# References.net
KiCad netlist of a schematic drawn in Altium Designer
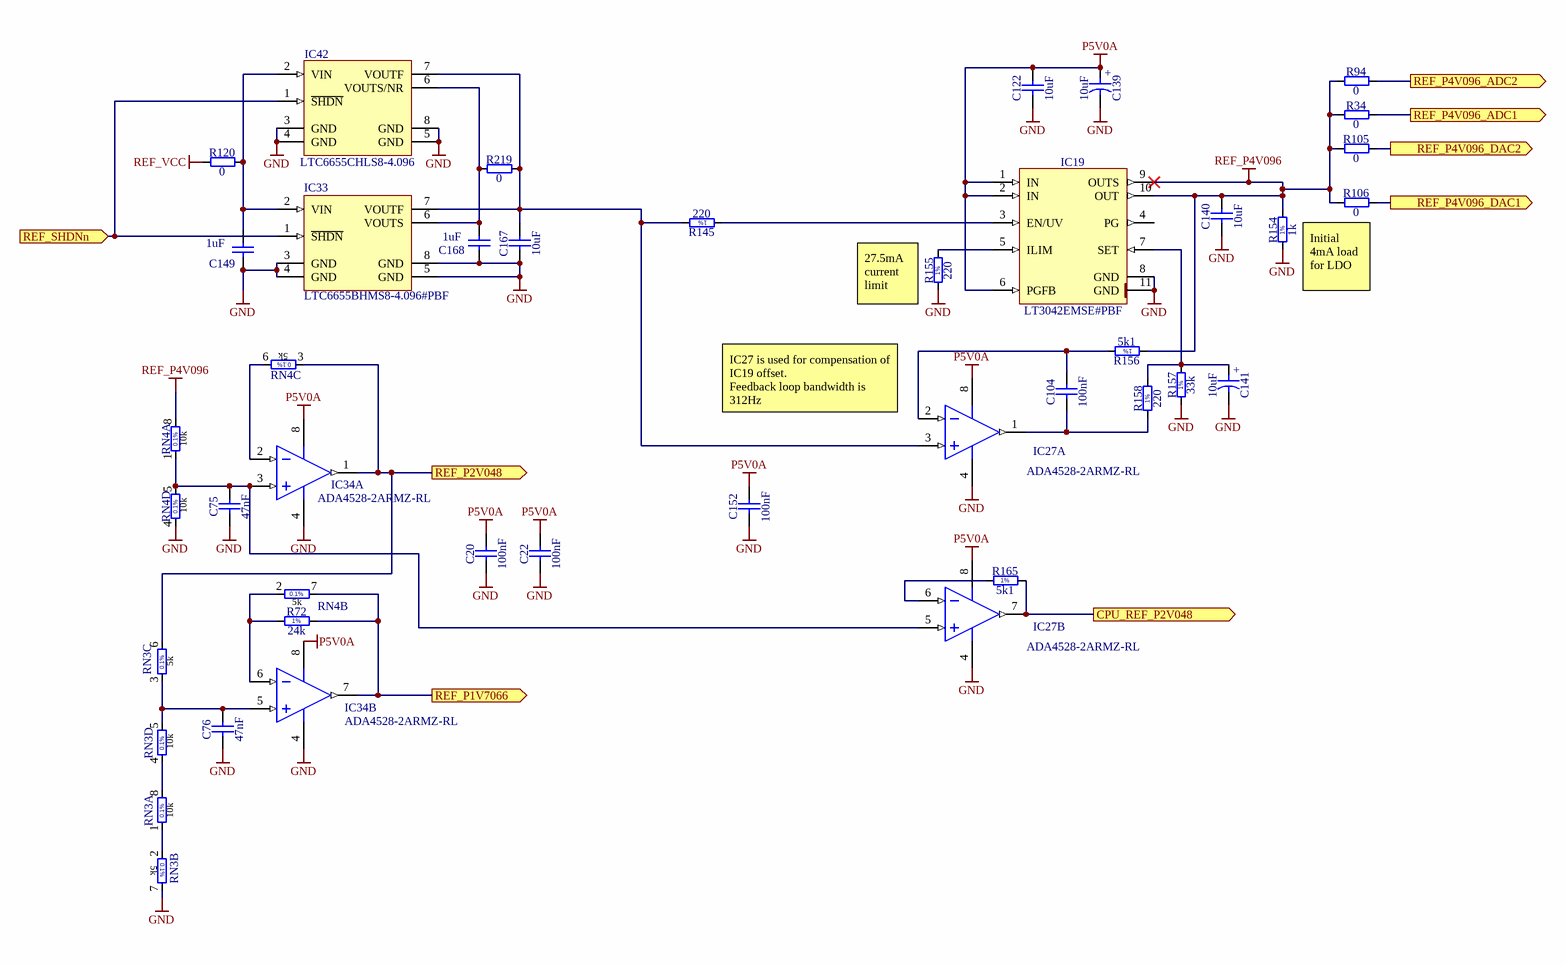
[diagram p0: References.SchDoc]

(export (version "E")
  (design (tool "Eeschema 10.0.6"))
  (components
    (comp (ref "C20")
      (value "100nF")
      (footprint "CAPC1005X55N")
      (description "Non-polarised capacitor")
      (fields
        (field (name "PART NUMBER") "CC0402_100NF_16V_10%_X5R")
        (field (name "VOLTAGE") "16V")
        (field (name "AUTHOR") "CERN DEM JLC")
      )
      (libsource (lib "Capacitors") (part "Capacitor - non polarized"))
    )
    (comp (ref "C22")
      (value "100nF")
      (footprint "CAPC1005X55N")
      (description "Non-polarised capacitor")
      (fields
        (field (name "PART NUMBER") "CC0402_100NF_16V_10%_X5R")
        (field (name "VOLTAGE") "16V")
        (field (name "AUTHOR") "CERN DEM JLC")
      )
      (libsource (lib "Capacitors") (part "Capacitor - non polarized"))
    )
    (comp (ref "C75")
      (value "47nF")
      (footprint "CAPC2012X135N")
      (description "Non-polarised capacitor")
      (fields
        (field (name "PART NUMBER") "CC0805_47NF_25V_5%_C0G")
        (field (name "VOLTAGE") "25V")
        (field (name "AUTHOR") "CERN DEM JLC")
      )
      (libsource (lib "Capacitors") (part "Capacitor - non polarized"))
    )
    (comp (ref "C76")
      (value "47nF")
      (footprint "CAPC2012X135N")
      (description "Non-polarised capacitor")
      (fields
        (field (name "PART NUMBER") "CC0805_47NF_25V_5%_C0G")
        (field (name "VOLTAGE") "25V")
        (field (name "AUTHOR") "CERN DEM JLC")
      )
      (libsource (lib "Capacitors") (part "Capacitor - non polarized"))
    )
    (comp (ref "C104")
      (value "100nF")
      (footprint "CAPC1005X55N")
      (description "Non-polarised capacitor")
      (fields
        (field (name "PART NUMBER") "CC0402_100NF_16V_10%_X5R")
        (field (name "VOLTAGE") "16V")
        (field (name "AUTHOR") "CERN DEM JLC")
      )
      (libsource (lib "Capacitors") (part "Capacitor - non polarized"))
    )
    (comp (ref "C122")
      (value "10uF")
      (footprint "CAPC2012X95N")
      (description "Non-polarised capacitor")
      (fields
        (field (name "PART NUMBER") "CC0805_10UF_25V_10%_X5R")
        (field (name "VOLTAGE") "25V")
        (field (name "AUTHOR") "CERN DEM JLC")
      )
      (libsource (lib "Capacitors") (part "Capacitor - non polarized"))
    )
    (comp (ref "C139")
      (value "10uF")
      (footprint "CAPMP3216X180N")
      (description "Polarised capacitor")
      (fields
        (field (name "PART NUMBER") "CTE3216-18_10UF_16V_20%_AVX_TCJ")
        (field (name "VOLTAGE") "16V")
        (field (name "AUTHOR") "CERN DEM JLC")
      )
      (libsource (lib "Capacitors") (part "Capacitor - polarized"))
    )
    (comp (ref "C140")
      (value "10uF")
      (footprint "CAPC2012X95N")
      (description "Non-polarised capacitor")
      (fields
        (field (name "PART NUMBER") "CC0805_10UF_25V_10%_X5R")
        (field (name "VOLTAGE") "25V")
        (field (name "AUTHOR") "CERN DEM JLC")
      )
      (libsource (lib "Capacitors") (part "Capacitor - non polarized"))
    )
    (comp (ref "C141")
      (value "10uF")
      (footprint "CAPMP3216X180N")
      (description "Polarised capacitor")
      (fields
        (field (name "PART NUMBER") "CTE3216-18_10UF_16V_20%_AVX_TCJ")
        (field (name "VOLTAGE") "16V")
        (field (name "AUTHOR") "CERN DEM JLC")
      )
      (libsource (lib "Capacitors") (part "Capacitor - polarized"))
    )
    (comp (ref "C149")
      (value "1uF")
      (footprint "CAPC1608X87N")
      (description "Non-polarised capacitor")
      (fields
        (field (name "PART NUMBER") "CC0603_1UF_25V_10%_X7R")
        (field (name "VOLTAGE") "25V")
        (field (name "AUTHOR") "CERN DEM JLC")
      )
      (libsource (lib "Capacitors") (part "Capacitor - non polarized"))
    )
    (comp (ref "C152")
      (value "100nF")
      (footprint "CAPC1005X55N")
      (description "Non-polarised capacitor")
      (fields
        (field (name "PART NUMBER") "CC0402_100NF_16V_10%_X5R")
        (field (name "VOLTAGE") "16V")
        (field (name "AUTHOR") "CERN DEM JLC")
      )
      (libsource (lib "Capacitors") (part "Capacitor - non polarized"))
    )
    (comp (ref "C167")
      (value "10uF")
      (footprint "CAPC2012X95N")
      (description "Non-polarised capacitor")
      (fields
        (field (name "PART NUMBER") "CC0805_10UF_25V_10%_X5R")
        (field (name "VOLTAGE") "25V")
        (field (name "AUTHOR") "CERN DEM JLC")
      )
      (libsource (lib "Capacitors") (part "Capacitor - non polarized"))
    )
    (comp (ref "C168")
      (value "1uF")
      (footprint "CAPC1608X87N")
      (description "Non-polarised capacitor")
      (fields
        (field (name "PART NUMBER") "CC0603_1UF_25V_10%_X7R")
        (field (name "VOLTAGE") "25V")
        (field (name "AUTHOR") "CERN DEM JLC")
      )
      (libsource (lib "Capacitors") (part "Capacitor - non polarized"))
    )
    (comp (ref "IC19")
      (value "LT3042EMSE#PBF")
      (footprint "SOP50P490X110-11N-R168X198")
      (description "20V, 200mA, Ultralow Noise, Ultrahigh PSRR RF Linear Regulator")
      (fields (field (name "MANUFACTURER") "LINEAR TECHNOLOGY") (field (name "AUTHOR") "CERN DEM MR"))
      (libsource (lib "ICs And Semiconductors") (part "LT3042"))
    )
    (comp (ref "IC27")
      (value "ADA4528-2ARMZ-RL")
      (footprint "ADI-RM-8_N")
      (fields (field (name "GENERIC PART NUMBER") "ADA4528-2") (field (name "MANUFACTURER") "Analog Devices"))
      (libsource (lib "Altium Content Vault") (part "ADI-ADA4000-2-X-8"))
    )
    (comp (ref "IC33")
      (value "LTC6655BHMS8-4.096#PBF")
      (footprint "SOP65P490X110-8N")
      (description "0.25ppm Noise, Low Drift Precision Buffered Voltage Reference")
      (fields (field (name "MANUFACTURER") "LINEAR TECHNOLOGY") (field (name "AUTHOR") "GK"))
      (libsource (lib "LIBRARY_SCH") (part "REF_LTC6655"))
    )
    (comp (ref "IC34")
      (value "ADA4528-2ARMZ-RL")
      (footprint "ADI-RM-8_N")
      (fields (field (name "GENERIC PART NUMBER") "ADA4528-2") (field (name "MANUFACTURER") "Analog Devices"))
      (libsource (lib "Altium Content Vault") (part "ADI-ADA4000-2-X-8"))
    )
    (comp (ref "IC42")
      (value "LTC6655CHLS8-4.096")
      (footprint "LCCS127P500X500X145-8N")
      (description "4.096, 1uA Precision Voltage Reference")
      (fields
        (field (name "PART NUMBER") "LTC6655CHLS8-4.096#PBF")
        (field (name "MANUFACTURER") "LINEAR TECHNOLOGY")
        (field (name "AUTHOR") "GK")
      )
      (libsource (lib "ICs_Analog_Interfaces") (part "REF_LTC6655CHLS8-4.096"))
    )
    (comp (ref "R34")
      (value "0")
      (footprint "RESC1005X40N")
      (description "Resistor")
      (fields
        (field (name "PART NUMBER") "R0402_0R_JUMPER")
        (field (name "MANUFACTURER") "GENERIC")
        (field (name "AUTHOR") "CERN DEM JLC")
      )
      (libsource (lib "Resistors") (part "Resistor"))
    )
    (comp (ref "R72")
      (value "24k")
      (footprint "RESC1608X55N")
      (description "Resistor - 1%")
      (fields
        (field (name "PART NUMBER") "R0603_24K_1%_0.1W_100PPM")
        (field (name "POWER") "0.1W")
        (field (name "AUTHOR") "CERN DEM JLC")
      )
      (libsource (lib "Resistors") (part "Resistor - 1%"))
    )
    (comp (ref "R94")
      (value "0")
      (footprint "RESC1005X40N")
      (description "Resistor")
      (fields
        (field (name "PART NUMBER") "R0402_0R_JUMPER")
        (field (name "MANUFACTURER") "GENERIC")
        (field (name "AUTHOR") "CERN DEM JLC")
      )
      (libsource (lib "Resistors") (part "Resistor"))
    )
    (comp (ref "R105")
      (value "0")
      (footprint "RESC1005X40N")
      (description "Resistor")
      (fields
        (field (name "PART NUMBER") "R0402_0R_JUMPER")
        (field (name "MANUFACTURER") "GENERIC")
        (field (name "AUTHOR") "CERN DEM JLC")
      )
      (libsource (lib "Resistors") (part "Resistor"))
    )
    (comp (ref "R106")
      (value "0")
      (footprint "RESC1005X40N")
      (description "Resistor")
      (fields
        (field (name "PART NUMBER") "R0402_0R_JUMPER")
        (field (name "MANUFACTURER") "GENERIC")
        (field (name "AUTHOR") "CERN DEM JLC")
      )
      (libsource (lib "Resistors") (part "Resistor"))
    )
    (comp (ref "R120")
      (value "0")
      (footprint "RESC1005X40N")
      (description "Resistor")
      (fields
        (field (name "PART NUMBER") "R0402_0R_JUMPER")
        (field (name "MANUFACTURER") "GENERIC")
        (field (name "AUTHOR") "CERN DEM JLC")
      )
      (libsource (lib "Resistors") (part "Resistor"))
    )
    (comp (ref "R145")
      (value "220")
      (footprint "RESC1608X55N")
      (description "Resistor - 1%")
      (fields
        (field (name "PART NUMBER") "R0603_220R_1%_0.1W_100PPM")
        (field (name "POWER") "0.1W")
        (field (name "AUTHOR") "CERN DEM JLC")
      )
      (libsource (lib "Resistors") (part "Resistor - 1%"))
    )
    (comp (ref "R154")
      (value "1k")
      (footprint "RESC1608X55N")
      (description "Resistor - 1%")
      (fields
        (field (name "PART NUMBER") "R0603_1K_1%_0.1W_100PPM")
        (field (name "POWER") "0.1W")
        (field (name "AUTHOR") "CERN DEM JLC")
      )
      (libsource (lib "Resistors") (part "Resistor - 1%"))
    )
    (comp (ref "R155")
      (value "220")
      (footprint "RESC1608X55N")
      (description "Resistor - 1%")
      (fields
        (field (name "PART NUMBER") "R0603_220R_1%_0.1W_100PPM")
        (field (name "POWER") "0.1W")
        (field (name "AUTHOR") "CERN DEM JLC")
      )
      (libsource (lib "Resistors") (part "Resistor - 1%"))
    )
    (comp (ref "R156")
      (value "5k1")
      (footprint "RESC1005X40N")
      (description "Resistor - 1%")
      (fields
        (field (name "PART NUMBER") "R0402_5K1_1%_0.0625W_100PPM")
        (field (name "POWER") "0.0625W")
        (field (name "AUTHOR") "CERN DEM JLC")
      )
      (libsource (lib "Resistors") (part "Resistor - 1%"))
    )
    (comp (ref "R157")
      (value "33k")
      (footprint "RESC1005X40N")
      (description "Resistor - 1%")
      (fields
        (field (name "PART NUMBER") "R0402_33K_1%_0.0625W_100PPM")
        (field (name "POWER") "0.0625W")
        (field (name "AUTHOR") "CERN DEM JLC")
      )
      (libsource (lib "Resistors") (part "Resistor - 1%"))
    )
    (comp (ref "R158")
      (value "220")
      (footprint "RESC1608X55N")
      (description "Resistor - 1%")
      (fields
        (field (name "PART NUMBER") "R0603_220R_1%_0.1W_100PPM")
        (field (name "POWER") "0.1W")
        (field (name "AUTHOR") "CERN DEM JLC")
      )
      (libsource (lib "Resistors") (part "Resistor - 1%"))
    )
    (comp (ref "R165")
      (value "5k1")
      (footprint "RESC1005X40N")
      (description "Resistor - 1%")
      (fields
        (field (name "PART NUMBER") "R0402_5K1_1%_0.0625W_100PPM")
        (field (name "POWER") "0.0625W")
        (field (name "AUTHOR") "CERN DEM JLC")
      )
      (libsource (lib "Resistors") (part "Resistor - 1%"))
    )
    (comp (ref "R219")
      (value "0")
      (footprint "RESC1005X40N")
      (description "Resistor")
      (fields
        (field (name "PART NUMBER") "R0402_0R_JUMPER")
        (field (name "MANUFACTURER") "GENERIC")
        (field (name "AUTHOR") "CERN DEM JLC")
      )
      (libsource (lib "Resistors") (part "Resistor"))
    )
    (comp (ref "RN3")
      (value "10k 5K 5K 10K")
      (footprint "SOIC127P600X175-8N")
      (description "DIL8 Resistor Network 4 Resistors 10k-5k-5k-10k 0.1%")
      (fields
        (field (name "PART NUMBER") "RN_10K_5K_VISHAY_AORN2-1AT3")
        (field (name "POWER") "4x0.1W")
        (field (name "AUTHOR") "CERN DEM JLC")
      )
      (libsource (lib "Resistors") (part "RN DIL8_4xR_10k-5k-5k-10k_0.1%"))
    )
    (comp (ref "RN4")
      (value "10k 5K 5K 10K")
      (footprint "SOIC127P600X175-8N")
      (description "DIL8 Resistor Network 4 Resistors 10k-5k-5k-10k 0.1%")
      (fields
        (field (name "PART NUMBER") "RN_10K_5K_VISHAY_AORN2-1AT3")
        (field (name "POWER") "4x0.1W")
        (field (name "AUTHOR") "CERN DEM JLC")
      )
      (libsource (lib "Resistors") (part "RN DIL8_4xR_10k-5k-5k-10k_0.1%"))
    )
  )
  (nets
    (net (code "1") (name "/CPU_REF_P2V048") (class "Default")
      (node (ref "IC27") (pin "7") (pinfunction "OUT_B_7") (pintype "output"))
      (node (ref "R165") (pin "2") (pinfunction "2_2") (pintype "passive"))
    )
    (net (code "2") (name "/REF_P1V7066") (class "Default")
      (node (ref "IC34") (pin "7") (pinfunction "OUT_B_7") (pintype "output"))
      (node (ref "R72") (pin "2") (pinfunction "2_2") (pintype "passive"))
      (node (ref "RN4") (pin "7") (pinfunction "7_7") (pintype "passive"))
    )
    (net (code "3") (name "/REF_P2V048") (class "Default")
      (node (ref "IC34") (pin "1") (pinfunction "OUT_A_1") (pintype "output"))
      (node (ref "RN3") (pin "6") (pinfunction "6_6") (pintype "passive"))
      (node (ref "RN4") (pin "3") (pinfunction "3_3") (pintype "passive"))
    )
    (net (code "4") (name "/REF_P4V096_ADC1") (class "Default")
      (node (ref "R34") (pin "2") (pinfunction "2_2") (pintype "passive"))
    )
    (net (code "5") (name "/REF_P4V096_ADC2") (class "Default")
      (node (ref "R94") (pin "2") (pinfunction "2_2") (pintype "passive"))
    )
    (net (code "6") (name "/REF_P4V096_DAC1") (class "Default")
      (node (ref "R106") (pin "2") (pinfunction "2_2") (pintype "passive"))
    )
    (net (code "7") (name "/REF_P4V096_DAC2") (class "Default")
      (node (ref "R105") (pin "2") (pinfunction "2_2") (pintype "passive"))
    )
    (net (code "8") (name "/REF_SHDNn") (class "Default")
      (node (ref "IC33") (pin "1") (pinfunction "~{SHDN}_1") (pintype "input"))
      (node (ref "IC42") (pin "1") (pinfunction "~{SHDN}_1") (pintype "input"))
    )
    (net (code "9") (name "GND") (class "Default")
      (node (ref "C122") (pin "1") (pinfunction "1_1") (pintype "passive"))
      (node (ref "C139") (pin "2") (pinfunction "2_2") (pintype "passive"))
      (node (ref "C140") (pin "1") (pinfunction "1_1") (pintype "passive"))
      (node (ref "C141") (pin "2") (pinfunction "2_2") (pintype "passive"))
      (node (ref "C149") (pin "1") (pinfunction "1_1") (pintype "passive"))
      (node (ref "C152") (pin "1") (pinfunction "1_1") (pintype "passive"))
      (node (ref "C167") (pin "1") (pinfunction "1_1") (pintype "passive"))
      (node (ref "C168") (pin "1") (pinfunction "1_1") (pintype "passive"))
      (node (ref "C20") (pin "1") (pinfunction "1_1") (pintype "passive"))
      (node (ref "C22") (pin "1") (pinfunction "1_1") (pintype "passive"))
      (node (ref "C75") (pin "1") (pinfunction "1_1") (pintype "passive"))
      (node (ref "C76") (pin "1") (pinfunction "1_1") (pintype "passive"))
      (node (ref "IC19") (pin "11") (pinfunction "GND_11") (pintype "power_in"))
      (node (ref "IC19") (pin "8") (pinfunction "GND_8") (pintype "power_in"))
      (node (ref "IC27") (pin "4") (pinfunction "-V_4") (pintype "power_in"))
      (node (ref "IC33") (pin "3") (pinfunction "GND_3") (pintype "power_in"))
      (node (ref "IC33") (pin "4") (pinfunction "GND_4") (pintype "power_in"))
      (node (ref "IC33") (pin "5") (pinfunction "GND_5") (pintype "power_in"))
      (node (ref "IC33") (pin "8") (pinfunction "GND_8") (pintype "power_in"))
      (node (ref "IC34") (pin "4") (pinfunction "-V_4") (pintype "power_in"))
      (node (ref "IC42") (pin "3") (pinfunction "GND_3") (pintype "power_in"))
      (node (ref "IC42") (pin "4") (pinfunction "GND_4") (pintype "power_in"))
      (node (ref "IC42") (pin "5") (pinfunction "GND_5") (pintype "power_in"))
      (node (ref "IC42") (pin "8") (pinfunction "GND_8") (pintype "power_in"))
      (node (ref "R154") (pin "1") (pinfunction "1_1") (pintype "passive"))
      (node (ref "R155") (pin "1") (pinfunction "1_1") (pintype "passive"))
      (node (ref "R157") (pin "1") (pinfunction "1_1") (pintype "passive"))
      (node (ref "RN3") (pin "7") (pinfunction "7_7") (pintype "passive"))
      (node (ref "RN4") (pin "4") (pinfunction "4_4") (pintype "passive"))
    )
    (net (code "10") (name "Net-(IC19-EN{slash}UV)") (class "Default")
      (node (ref "IC19") (pin "3") (pinfunction "EN/UV_3") (pintype "input"))
      (node (ref "R145") (pin "1") (pinfunction "1_1") (pintype "passive"))
    )
    (net (code "11") (name "Net-(IC19-ILIM)") (class "Default")
      (node (ref "IC19") (pin "5") (pinfunction "ILIM_5") (pintype "input"))
      (node (ref "R155") (pin "2") (pinfunction "2_2") (pintype "passive"))
    )
    (net (code "12") (name "Net-(IC19-SET)") (class "Default")
      (node (ref "C141") (pin "1") (pinfunction "1_1") (pintype "passive"))
      (node (ref "IC19") (pin "7") (pinfunction "SET_7") (pintype "input"))
      (node (ref "R157") (pin "2") (pinfunction "2_2") (pintype "passive"))
      (node (ref "R158") (pin "2") (pinfunction "2_2") (pintype "passive"))
    )
    (net (code "13") (name "Net-(IC27A-+IN_A)") (class "Default")
      (node (ref "C167") (pin "2") (pinfunction "2_2") (pintype "passive"))
      (node (ref "IC27") (pin "3") (pinfunction "+IN_A_3") (pintype "input"))
      (node (ref "IC33") (pin "7") (pinfunction "VOUTF_7") (pintype "power_in"))
      (node (ref "IC42") (pin "7") (pinfunction "VOUTF_7") (pintype "power_in"))
      (node (ref "R145") (pin "2") (pinfunction "2_2") (pintype "passive"))
      (node (ref "R219") (pin "2") (pinfunction "2_2") (pintype "passive"))
    )
    (net (code "14") (name "Net-(IC27A--IN_A)") (class "Default")
      (node (ref "C104") (pin "2") (pinfunction "2_2") (pintype "passive"))
      (node (ref "IC27") (pin "2") (pinfunction "-IN_A_2") (pintype "input"))
      (node (ref "R156") (pin "2") (pinfunction "2_2") (pintype "passive"))
    )
    (net (code "15") (name "Net-(IC27A-OUT_A)") (class "Default")
      (node (ref "C104") (pin "1") (pinfunction "1_1") (pintype "passive"))
      (node (ref "IC27") (pin "1") (pinfunction "OUT_A_1") (pintype "output"))
      (node (ref "R158") (pin "1") (pinfunction "1_1") (pintype "passive"))
    )
    (net (code "16") (name "Net-(IC27B-+IN_B)") (class "Default")
      (node (ref "C75") (pin "2") (pinfunction "2_2") (pintype "passive"))
      (node (ref "IC27") (pin "5") (pinfunction "+IN_B_5") (pintype "input"))
      (node (ref "IC34") (pin "3") (pinfunction "+IN_A_3") (pintype "input"))
      (node (ref "RN4") (pin "1") (pinfunction "1_1") (pintype "passive"))
      (node (ref "RN4") (pin "5") (pinfunction "5_5") (pintype "passive"))
    )
    (net (code "17") (name "Net-(IC27B--IN_B)") (class "Default")
      (node (ref "IC27") (pin "6") (pinfunction "-IN_B_6") (pintype "input"))
      (node (ref "R165") (pin "1") (pinfunction "1_1") (pintype "passive"))
    )
    (net (code "18") (name "Net-(IC33-VIN)") (class "Default")
      (node (ref "C149") (pin "2") (pinfunction "2_2") (pintype "passive"))
      (node (ref "IC33") (pin "2") (pinfunction "VIN_2") (pintype "input"))
      (node (ref "IC42") (pin "2") (pinfunction "VIN_2") (pintype "input"))
      (node (ref "R120") (pin "2") (pinfunction "2_2") (pintype "passive"))
    )
    (net (code "19") (name "Net-(IC33-VOUTS)") (class "Default")
      (node (ref "C168") (pin "2") (pinfunction "2_2") (pintype "passive"))
      (node (ref "IC33") (pin "6") (pinfunction "VOUTS_6") (pintype "power_in"))
      (node (ref "IC42") (pin "6") (pinfunction "VOUTS/NR_6") (pintype "power_in"))
      (node (ref "R219") (pin "1") (pinfunction "1_1") (pintype "passive"))
    )
    (net (code "20") (name "Net-(IC34A--IN_A)") (class "Default")
      (node (ref "IC34") (pin "2") (pinfunction "-IN_A_2") (pintype "input"))
      (node (ref "RN4") (pin "6") (pinfunction "6_6") (pintype "passive"))
    )
    (net (code "21") (name "Net-(IC34B-+IN_B)") (class "Default")
      (node (ref "C76") (pin "2") (pinfunction "2_2") (pintype "passive"))
      (node (ref "IC34") (pin "5") (pinfunction "+IN_B_5") (pintype "input"))
      (node (ref "RN3") (pin "3") (pinfunction "3_3") (pintype "passive"))
      (node (ref "RN3") (pin "5") (pinfunction "5_5") (pintype "passive"))
    )
    (net (code "22") (name "Net-(IC34B--IN_B)") (class "Default")
      (node (ref "IC34") (pin "6") (pinfunction "-IN_B_6") (pintype "input"))
      (node (ref "R72") (pin "1") (pinfunction "1_1") (pintype "passive"))
      (node (ref "RN4") (pin "2") (pinfunction "2_2") (pintype "passive"))
    )
    (net (code "23") (name "Net-(RN3-Pad1)") (class "Default")
      (node (ref "RN3") (pin "1") (pinfunction "1_1") (pintype "passive"))
      (node (ref "RN3") (pin "2") (pinfunction "2_2") (pintype "passive"))
    )
    (net (code "24") (name "Net-(RN3-Pad4)") (class "Default")
      (node (ref "RN3") (pin "4") (pinfunction "4_4") (pintype "passive"))
      (node (ref "RN3") (pin "8") (pinfunction "8_8") (pintype "passive"))
    )
    (net (code "25") (name "P5V0A") (class "Default")
      (node (ref "C122") (pin "2") (pinfunction "2_2") (pintype "passive"))
      (node (ref "C139") (pin "1") (pinfunction "1_1") (pintype "passive"))
      (node (ref "C152") (pin "2") (pinfunction "2_2") (pintype "passive"))
      (node (ref "C20") (pin "2") (pinfunction "2_2") (pintype "passive"))
      (node (ref "C22") (pin "2") (pinfunction "2_2") (pintype "passive"))
      (node (ref "IC19") (pin "1") (pinfunction "IN_1") (pintype "input"))
      (node (ref "IC19") (pin "2") (pinfunction "IN_2") (pintype "input"))
      (node (ref "IC19") (pin "6") (pinfunction "PGFB_6") (pintype "input"))
      (node (ref "IC27") (pin "8") (pinfunction "+V_8") (pintype "power_in"))
      (node (ref "IC34") (pin "8") (pinfunction "+V_8") (pintype "power_in"))
    )
    (net (code "26") (name "REF_P4V096") (class "Default")
      (node (ref "C140") (pin "2") (pinfunction "2_2") (pintype "passive"))
      (node (ref "IC19") (pin "10") (pinfunction "OUT_10") (pintype "output"))
      (node (ref "IC19") (pin "9") (pinfunction "OUTS_9") (pintype "output"))
      (node (ref "R105") (pin "1") (pinfunction "1_1") (pintype "passive"))
      (node (ref "R106") (pin "1") (pinfunction "1_1") (pintype "passive"))
      (node (ref "R154") (pin "2") (pinfunction "2_2") (pintype "passive"))
      (node (ref "R156") (pin "1") (pinfunction "1_1") (pintype "passive"))
      (node (ref "R34") (pin "1") (pinfunction "1_1") (pintype "passive"))
      (node (ref "R94") (pin "1") (pinfunction "1_1") (pintype "passive"))
      (node (ref "RN4") (pin "8") (pinfunction "8_8") (pintype "passive"))
    )
    (net (code "27") (name "REF_VCC") (class "Default")
      (node (ref "R120") (pin "1") (pinfunction "1_1") (pintype "passive"))
    )
    (net (code "28") (name "unconnected-(IC19-PG-Pad4)") (class "Default")
      (node (ref "IC19") (pin "4") (pinfunction "PG_4") (pintype "output"))
    )
  )
)
